# SparkFun_NEO-D9S.net
KiCad netlist of a schematic drawn in EAGLE
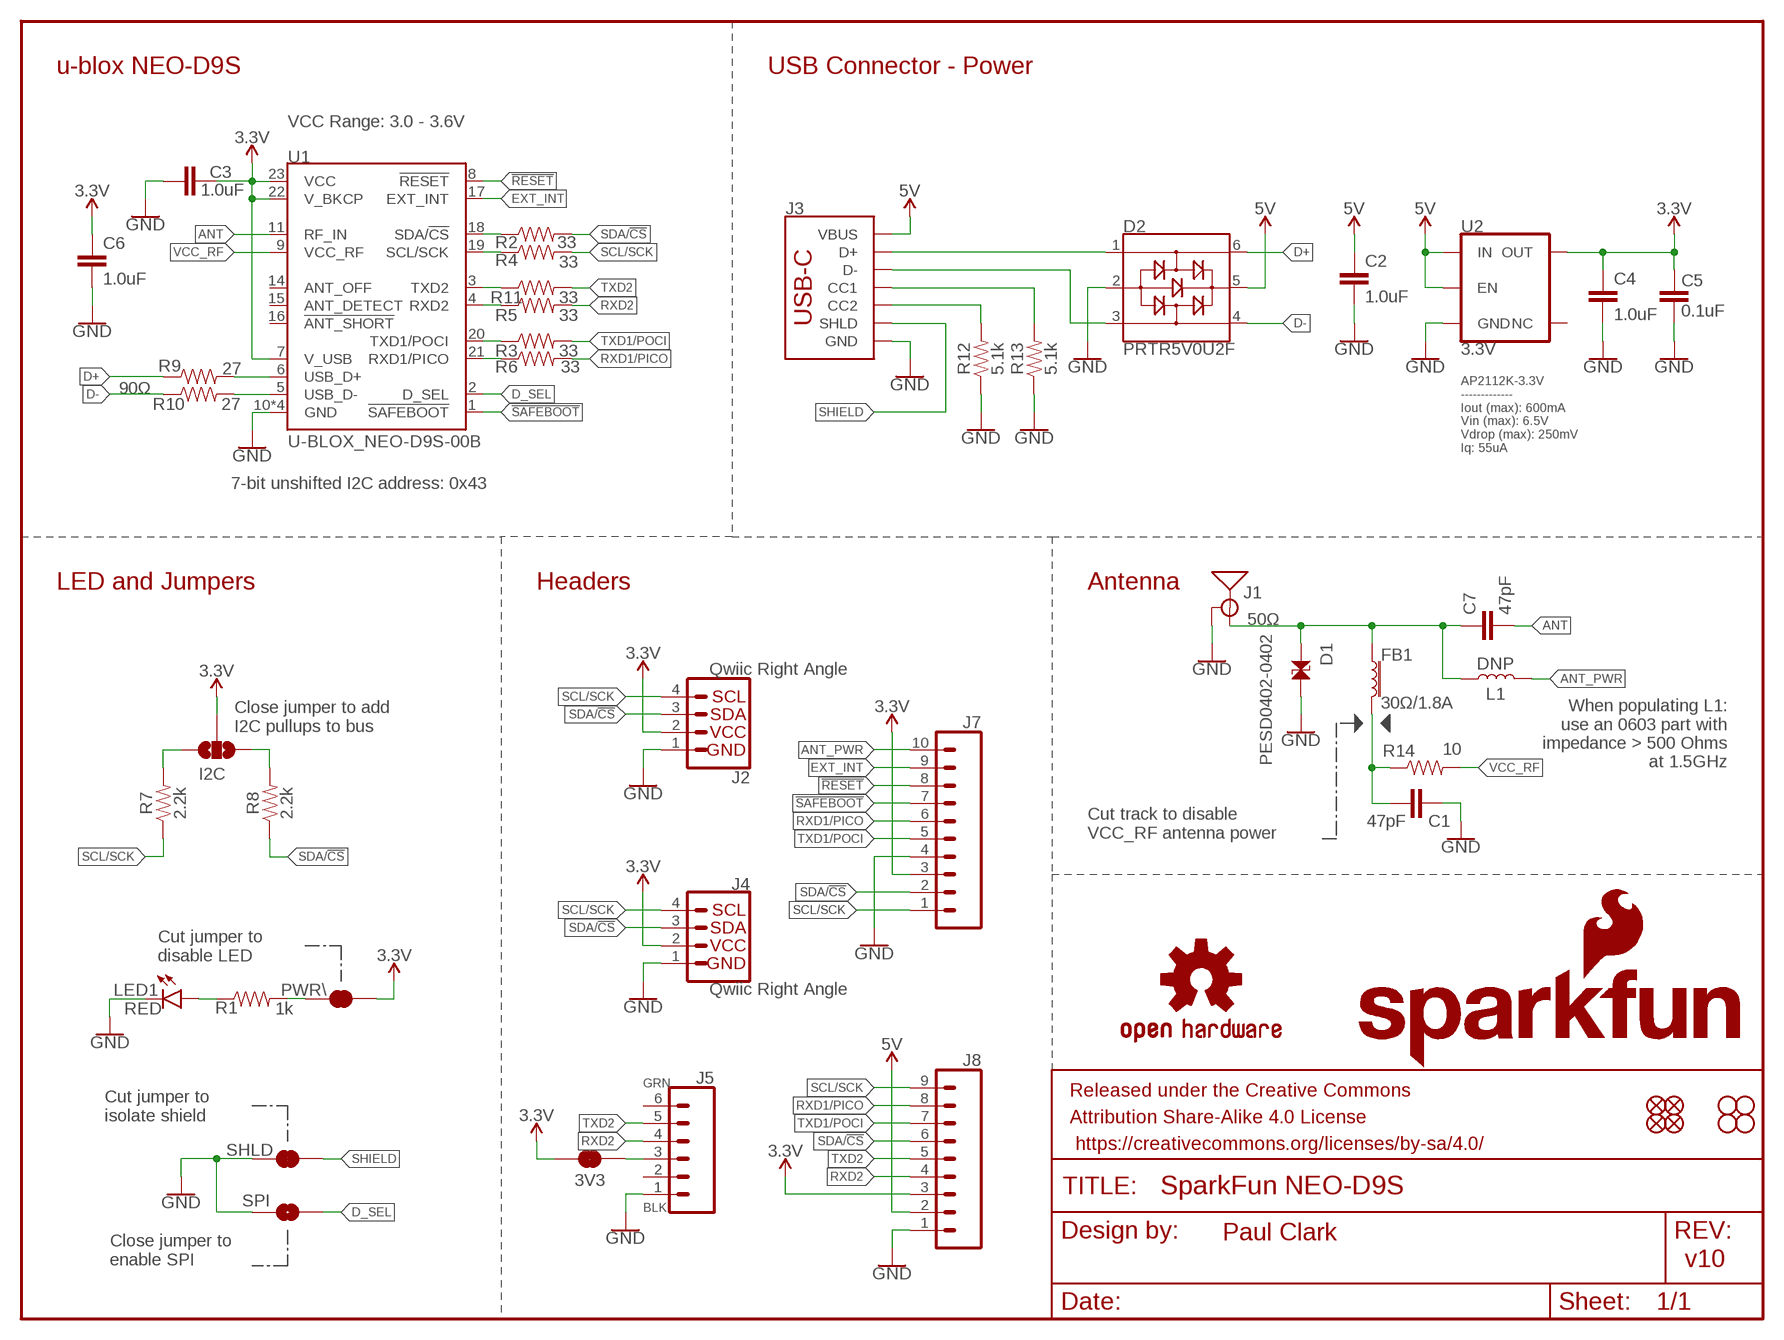
[diagram p0: schematic, sheet 1]

(export (version "E")
  (design (tool "Eeschema 10.0.6"))
  (components
    (comp (ref "3V3")
      (value "JUMPER-SMT_2_NC_TRACE_SILK")
      (footprint "eagle-import:SMT-JUMPER_2_NC_TRACE_SILK")
      (libsource (lib "eagle-import") (part "JUMPER-SMT_2_NC_TRACE_SILK"))
    )
    (comp (ref "C1")
      (value "47pF")
      (footprint "eagle-import:0603")
      (libsource (lib "eagle-import") (part "47PF-0603-50V-5%"))
    )
    (comp (ref "C2")
      (value "1.0uF")
      (footprint "eagle-import:0603")
      (libsource (lib "eagle-import") (part "1.0UF-0603-16V-10%"))
    )
    (comp (ref "C3")
      (value "1.0uF")
      (footprint "eagle-import:0603")
      (libsource (lib "eagle-import") (part "1.0UF-0603-16V-10%"))
    )
    (comp (ref "C4")
      (value "1.0uF")
      (footprint "eagle-import:0603")
      (libsource (lib "eagle-import") (part "1.0UF-0603-16V-10%"))
    )
    (comp (ref "C5")
      (value "0.1uF")
      (footprint "eagle-import:0603")
      (libsource (lib "eagle-import") (part "0.1UF-0603-25V-(+80/-20%)"))
    )
    (comp (ref "C6")
      (value "1.0uF")
      (footprint "eagle-import:0603")
      (libsource (lib "eagle-import") (part "1.0UF-0603-16V-10%"))
    )
    (comp (ref "C7")
      (value "47pF")
      (footprint "eagle-import:0603")
      (libsource (lib "eagle-import") (part "47PF-0603-50V-5%"))
    )
    (comp (ref "D1")
      (value "PESD0402-0402")
      (footprint "eagle-import:0402")
      (fields
        (field (name "DIGIKEY_PART") "PESD0402-140CT-ND")
        (field (name "MOUSE_PART") "650-PESD0402-140")
      )
      (libsource (lib "eagle-import") (part "PESD0402-0402"))
    )
    (comp (ref "D2")
      (value "PRTR5V0U2F")
      (footprint "eagle-import:SOT886")
      (libsource (lib "eagle-import") (part "PRTR5V0U2F"))
    )
    (comp (ref "FB1")
      (value "30Ω/1.8A")
      (footprint "eagle-import:0603")
      (libsource (lib "eagle-import") (part "FERRITE_BEAD-0603"))
    )
    (comp (ref "FRAME1")
      (value "FRAME-LETTER")
      (footprint "eagle-import:CREATIVE_COMMONS")
      (libsource (lib "eagle-import") (part "FRAME-LETTER"))
    )
    (comp (ref "I2C")
      (value "JUMPER-SMT_3_NO_SILK")
      (footprint "eagle-import:SMT-JUMPER_3_NO_SILK")
      (libsource (lib "eagle-import") (part "JUMPER-SMT_3_NO_SILK"))
    )
    (comp (ref "J1")
      (value "ANTENNA-SMA-GROUNDEDEDGE_SMA")
      (footprint "eagle-import:SMA-EDGE")
      (libsource (lib "eagle-import") (part "ANTENNA-SMA-GROUNDEDEDGE_SMA"))
    )
    (comp (ref "J2")
      (value "Qwiic Right Angle")
      (footprint "eagle-import:JST04_1MM_RA")
      (libsource (lib "eagle-import") (part "I2C_STANDARDQWIIC"))
    )
    (comp (ref "J3")
      (value "USB_C_2-LAYER_PADS")
      (footprint "eagle-import:USB-C-16P-2LAYER-PADS")
      (libsource (lib "eagle-import") (part "USB_C_2-LAYER_PADS"))
    )
    (comp (ref "J4")
      (value "Qwiic Right Angle")
      (footprint "eagle-import:JST04_1MM_RA")
      (libsource (lib "eagle-import") (part "I2C_STANDARDQWIIC"))
    )
    (comp (ref "J5")
      (value "CONN_06NO_SILK_FEMALE_PTH")
      (footprint "eagle-import:1X06_NO_SILK")
      (libsource (lib "eagle-import") (part "CONN_06NO_SILK_FEMALE_PTH"))
    )
    (comp (ref "J7")
      (value "CONN_10NO_SILK_PTH_FEMALE")
      (footprint "eagle-import:1X10_NO_SILK")
      (libsource (lib "eagle-import") (part "CONN_10NO_SILK_PTH_FEMALE"))
    )
    (comp (ref "J8")
      (value "CONN_09NO_SILK")
      (footprint "eagle-import:1X09_NO_SILK")
      (libsource (lib "eagle-import") (part "CONN_09NO_SILK"))
    )
    (comp (ref "JP21")
      (value "FIDUCIALUFIDUCIAL")
      (footprint "eagle-import:MICRO-FIDUCIAL")
      (libsource (lib "eagle-import") (part "FIDUCIALUFIDUCIAL"))
    )
    (comp (ref "JP31")
      (value "STAND-OFF")
      (footprint "eagle-import:STAND-OFF")
      (libsource (lib "eagle-import") (part "STAND-OFF"))
    )
    (comp (ref "JP41")
      (value "STAND-OFF")
      (footprint "eagle-import:STAND-OFF")
      (libsource (lib "eagle-import") (part "STAND-OFF"))
    )
    (comp (ref "JP61")
      (value "FIDUCIALUFIDUCIAL")
      (footprint "eagle-import:MICRO-FIDUCIAL")
      (libsource (lib "eagle-import") (part "FIDUCIALUFIDUCIAL"))
    )
    (comp (ref "JP71")
      (value "FIDUCIALUFIDUCIAL")
      (footprint "eagle-import:MICRO-FIDUCIAL")
      (libsource (lib "eagle-import") (part "FIDUCIALUFIDUCIAL"))
    )
    (comp (ref "JP81")
      (value "FIDUCIALUFIDUCIAL")
      (footprint "eagle-import:MICRO-FIDUCIAL")
      (libsource (lib "eagle-import") (part "FIDUCIALUFIDUCIAL"))
    )
    (comp (ref "JP91")
      (value "STAND-OFF")
      (footprint "eagle-import:STAND-OFF")
      (libsource (lib "eagle-import") (part "STAND-OFF"))
    )
    (comp (ref "JP101")
      (value "STAND-OFF")
      (footprint "eagle-import:STAND-OFF")
      (libsource (lib "eagle-import") (part "STAND-OFF"))
    )
    (comp (ref "L1")
      (value "DNP")
      (footprint "eagle-import:0603_NO-CREAM")
      (libsource (lib "eagle-import") (part "DNP-0603_NO-CREAM"))
    )
    (comp (ref "LED1")
      (value "RED")
      (footprint "eagle-import:LED-0603")
      (libsource (lib "eagle-import") (part "LED-RED0603"))
    )
    (comp (ref "LOGO1")
      (value "OSHW-LOGOS")
      (footprint "eagle-import:OSHW-LOGO-S")
      (libsource (lib "eagle-import") (part "OSHW-LOGOS"))
    )
    (comp (ref "LOGO2")
      (value "SFE_LOGO_NAME_FLAME.1_INCH")
      (footprint "eagle-import:SFE_LOGO_NAME_FLAME_.1")
      (libsource (lib "eagle-import") (part "SFE_LOGO_NAME_FLAME.1_INCH"))
    )
    (comp (ref "LOGO3")
      (value "SFE_LOGO_NAME_FLAME.1_INCH")
      (footprint "eagle-import:SFE_LOGO_NAME_FLAME_.1")
      (libsource (lib "eagle-import") (part "SFE_LOGO_NAME_FLAME.1_INCH"))
    )
    (comp (ref "LOGO4")
      (value "OSHW-LOGOS")
      (footprint "eagle-import:OSHW-LOGO-S")
      (libsource (lib "eagle-import") (part "OSHW-LOGOS"))
    )
    (comp (ref "PWR\\")
      (value "JUMPER-SMT_2_NC_TRACE_SILK")
      (footprint "eagle-import:SMT-JUMPER_2_NC_TRACE_SILK")
      (libsource (lib "eagle-import") (part "JUMPER-SMT_2_NC_TRACE_SILK"))
    )
    (comp (ref "R1")
      (value "1k")
      (footprint "eagle-import:0603")
      (libsource (lib "eagle-import") (part "1KOHM-0603-1/10W-1%"))
    )
    (comp (ref "R2")
      (value "33")
      (footprint "eagle-import:0603")
      (libsource (lib "eagle-import") (part "33OHM-0603-1/10W-1%"))
    )
    (comp (ref "R3")
      (value "33")
      (footprint "eagle-import:0603")
      (libsource (lib "eagle-import") (part "33OHM-0603-1/10W-1%"))
    )
    (comp (ref "R4")
      (value "33")
      (footprint "eagle-import:0603")
      (libsource (lib "eagle-import") (part "33OHM-0603-1/10W-1%"))
    )
    (comp (ref "R5")
      (value "33")
      (footprint "eagle-import:0603")
      (libsource (lib "eagle-import") (part "33OHM-0603-1/10W-1%"))
    )
    (comp (ref "R6")
      (value "33")
      (footprint "eagle-import:0603")
      (libsource (lib "eagle-import") (part "33OHM-0603-1/10W-1%"))
    )
    (comp (ref "R7")
      (value "2.2k")
      (footprint "eagle-import:0603")
      (libsource (lib "eagle-import") (part "2.2KOHM-0603-1/10W-1%"))
    )
    (comp (ref "R8")
      (value "2.2k")
      (footprint "eagle-import:0603")
      (libsource (lib "eagle-import") (part "2.2KOHM-0603-1/10W-1%"))
    )
    (comp (ref "R9")
      (value "27")
      (footprint "eagle-import:0603")
      (libsource (lib "eagle-import") (part "27OHM-0603-1/10W-1%"))
    )
    (comp (ref "R10")
      (value "27")
      (footprint "eagle-import:0603")
      (libsource (lib "eagle-import") (part "27OHM-0603-1/10W-1%"))
    )
    (comp (ref "R11")
      (value "33")
      (footprint "eagle-import:0603")
      (libsource (lib "eagle-import") (part "33OHM-0603-1/10W-1%"))
    )
    (comp (ref "R12")
      (value "5.1k")
      (footprint "eagle-import:0603")
      (libsource (lib "eagle-import") (part "5.1KOHM5.1KOHM-0603-1/10W-1%"))
    )
    (comp (ref "R13")
      (value "5.1k")
      (footprint "eagle-import:0603")
      (libsource (lib "eagle-import") (part "5.1KOHM5.1KOHM-0603-1/10W-1%"))
    )
    (comp (ref "R14")
      (value "10")
      (footprint "eagle-import:0603")
      (libsource (lib "eagle-import") (part "10OHM-0603-1/10W-1%"))
    )
    (comp (ref "SHLD")
      (value "JUMPER-SMT_2_NC_TRACE_SILK")
      (footprint "eagle-import:SMT-JUMPER_2_NC_TRACE_SILK")
      (libsource (lib "eagle-import") (part "JUMPER-SMT_2_NC_TRACE_SILK"))
    )
    (comp (ref "SPI")
      (value "JUMPER-SMT_2_NO_SILK")
      (footprint "eagle-import:SMT-JUMPER_2_NO_SILK")
      (libsource (lib "eagle-import") (part "JUMPER-SMT_2_NO_SILK"))
    )
    (comp (ref "U1")
      (value "U-BLOX_NEO-D9S-00B")
      (footprint "eagle-import:NEO-M9N_M8T_M8U_D9S")
      (libsource (lib "eagle-import") (part "U-BLOX_NEO-D9S-00B"))
    )
    (comp (ref "U2")
      (value "3.3V")
      (footprint "eagle-import:SOT23-5")
      (libsource (lib "eagle-import") (part "V_REG_AP2112K-3.3V"))
    )
  )
  (nets
    (net (code "1") (name "/SDA{slash}~{CS}") (class "Default")
      (node (ref "J2") (pin "3") (pinfunction "3_3") (pintype "passive"))
      (node (ref "J4") (pin "3") (pinfunction "3_3") (pintype "passive"))
      (node (ref "J7") (pin "2") (pinfunction "2_2") (pintype "passive"))
      (node (ref "J8") (pin "6") (pinfunction "6_6") (pintype "passive"))
      (node (ref "R2") (pin "2") (pinfunction "2_2") (pintype "passive"))
      (node (ref "R8") (pin "1") (pinfunction "1_1") (pintype "passive"))
    )
    (net (code "2") (name "/~{RESET}") (class "Default")
      (node (ref "J7") (pin "8") (pinfunction "8_8") (pintype "passive"))
      (node (ref "U1") (pin "8") (pinfunction "~{RESET}_8") (pintype "input"))
    )
    (net (code "3") (name "/~{SAFEBOOT}") (class "Default")
      (node (ref "J7") (pin "7") (pinfunction "7_7") (pintype "passive"))
      (node (ref "U1") (pin "1") (pinfunction "~{SAFEBOOT}_1") (pintype "input"))
    )
    (net (code "4") (name "3.3V") (class "Default")
      (node (ref "3V3") (pin "2") (pinfunction "2_2") (pintype "passive"))
      (node (ref "C3") (pin "1") (pinfunction "1_1") (pintype "passive"))
      (node (ref "C4") (pin "1") (pinfunction "1_1") (pintype "passive"))
      (node (ref "C5") (pin "2") (pinfunction "2_2") (pintype "passive"))
      (node (ref "C6") (pin "1") (pinfunction "1_1") (pintype "passive"))
      (node (ref "I2C") (pin "2") (pinfunction "2_2") (pintype "passive"))
      (node (ref "J2") (pin "2") (pinfunction "2_2") (pintype "power_in"))
      (node (ref "J4") (pin "2") (pinfunction "2_2") (pintype "power_in"))
      (node (ref "J7") (pin "3") (pinfunction "3_3") (pintype "passive"))
      (node (ref "J8") (pin "3") (pinfunction "3_3") (pintype "passive"))
      (node (ref "PWR\\") (pin "2") (pinfunction "2_2") (pintype "passive"))
      (node (ref "U1") (pin "22") (pinfunction "V_BKCP_22") (pintype "power_in"))
      (node (ref "U1") (pin "23") (pinfunction "VCC_23") (pintype "power_in"))
      (node (ref "U1") (pin "7") (pinfunction "V_USB_7") (pintype "power_in"))
      (node (ref "U2") (pin "5") (pinfunction "OUT_5") (pintype "passive"))
    )
    (net (code "5") (name "5V") (class "Default")
      (node (ref "C2") (pin "1") (pinfunction "1_1") (pintype "passive"))
      (node (ref "D2") (pin "5") (pinfunction "5_5") (pintype "power_in"))
      (node (ref "J3") (pin "VBUS1") (pinfunction "VBUS_VBUS1") (pintype "bidirectional"))
      (node (ref "J3") (pin "VBUS2") (pinfunction "VBUS_VBUS2") (pintype "bidirectional"))
      (node (ref "J8") (pin "2") (pinfunction "2_2") (pintype "passive"))
      (node (ref "U2") (pin "1") (pinfunction "IN_1") (pintype "input"))
      (node (ref "U2") (pin "3") (pinfunction "EN_3") (pintype "input"))
    )
    (net (code "6") (name "ANT") (class "Default")
      (node (ref "C7") (pin "2") (pinfunction "2_2") (pintype "passive"))
      (node (ref "U1") (pin "11") (pinfunction "RF_IN_11") (pintype "input"))
    )
    (net (code "7") (name "ANT_PWR") (class "Default")
      (node (ref "J7") (pin "10") (pinfunction "10_10") (pintype "passive"))
      (node (ref "L1") (pin "2") (pinfunction "2_2") (pintype "passive"))
    )
    (net (code "8") (name "D+") (class "Default")
      (node (ref "D2") (pin "6") (pinfunction "6_6") (pintype "bidirectional"))
      (node (ref "R9") (pin "1") (pinfunction "1_1") (pintype "passive"))
    )
    (net (code "9") (name "D-") (class "Default")
      (node (ref "D2") (pin "4") (pinfunction "4_4") (pintype "bidirectional"))
      (node (ref "R10") (pin "1") (pinfunction "1_1") (pintype "passive"))
    )
    (net (code "10") (name "D_SEL") (class "Default")
      (node (ref "SPI") (pin "2") (pinfunction "2_2") (pintype "passive"))
      (node (ref "U1") (pin "2") (pinfunction "D_SEL_2") (pintype "input"))
    )
    (net (code "11") (name "EXT_INT") (class "Default")
      (node (ref "J7") (pin "9") (pinfunction "9_9") (pintype "passive"))
      (node (ref "U1") (pin "17") (pinfunction "EXT_INT_17") (pintype "input"))
    )
    (net (code "12") (name "GND") (class "Default")
      (node (ref "C1") (pin "2") (pinfunction "2_2") (pintype "passive"))
      (node (ref "C2") (pin "2") (pinfunction "2_2") (pintype "passive"))
      (node (ref "C3") (pin "2") (pinfunction "2_2") (pintype "passive"))
      (node (ref "C4") (pin "2") (pinfunction "2_2") (pintype "passive"))
      (node (ref "C5") (pin "1") (pinfunction "1_1") (pintype "passive"))
      (node (ref "C6") (pin "2") (pinfunction "2_2") (pintype "passive"))
      (node (ref "D1") (pin "2") (pinfunction "2_2") (pintype "bidirectional"))
      (node (ref "D2") (pin "2") (pinfunction "2_2") (pintype "power_in"))
      (node (ref "J1") (pin "GND@0") (pinfunction "GND_GND@0") (pintype "bidirectional"))
      (node (ref "J1") (pin "GND@1") (pinfunction "GND_GND@1") (pintype "bidirectional"))
      (node (ref "J1") (pin "GND@2") (pinfunction "GND_GND@2") (pintype "bidirectional"))
      (node (ref "J1") (pin "GND@3") (pinfunction "GND_GND@3") (pintype "bidirectional"))
      (node (ref "J2") (pin "1") (pinfunction "1_1") (pintype "power_in"))
      (node (ref "J3") (pin "GND") (pinfunction "GND_GND") (pintype "bidirectional"))
      (node (ref "J3") (pin "GND2") (pinfunction "GND_GND2") (pintype "bidirectional"))
      (node (ref "J4") (pin "1") (pinfunction "1_1") (pintype "power_in"))
      (node (ref "J5") (pin "1") (pinfunction "1_1") (pintype "passive"))
      (node (ref "J7") (pin "4") (pinfunction "4_4") (pintype "passive"))
      (node (ref "J8") (pin "1") (pinfunction "1_1") (pintype "passive"))
      (node (ref "LED1") (pin "C") (pinfunction "C_C") (pintype "passive"))
      (node (ref "R12") (pin "1") (pinfunction "1_1") (pintype "passive"))
      (node (ref "R13") (pin "1") (pinfunction "1_1") (pintype "passive"))
      (node (ref "SHLD") (pin "1") (pinfunction "1_1") (pintype "passive"))
      (node (ref "SPI") (pin "1") (pinfunction "1_1") (pintype "passive"))
      (node (ref "U1") (pin "10") (pinfunction "GND_10") (pintype "power_in"))
      (node (ref "U1") (pin "12") (pinfunction "GND_12") (pintype "power_in"))
      (node (ref "U1") (pin "13") (pinfunction "GND_13") (pintype "power_in"))
      (node (ref "U1") (pin "24") (pinfunction "GND_24") (pintype "power_in"))
      (node (ref "U2") (pin "2") (pinfunction "GND_2") (pintype "input"))
    )
    (net (code "13") (name "Net-(3V3-Pad1)") (class "Default")
      (node (ref "3V3") (pin "1") (pinfunction "1_1") (pintype "passive"))
      (node (ref "J5") (pin "3") (pinfunction "3_3") (pintype "passive"))
    )
    (net (code "14") (name "Net-(C1-Pad1)") (class "Default")
      (node (ref "C1") (pin "1") (pinfunction "1_1") (pintype "passive"))
      (node (ref "FB1") (pin "2") (pinfunction "2_2") (pintype "passive"))
      (node (ref "R14") (pin "1") (pinfunction "1_1") (pintype "passive"))
    )
    (net (code "15") (name "Net-(D2-Pad1)") (class "Default")
      (node (ref "D2") (pin "1") (pinfunction "1_1") (pintype "bidirectional"))
      (node (ref "J3") (pin "A6") (pinfunction "D+_A6") (pintype "bidirectional"))
      (node (ref "J3") (pin "B6") (pinfunction "D+_B6") (pintype "bidirectional"))
    )
    (net (code "16") (name "Net-(D2-Pad3)") (class "Default")
      (node (ref "D2") (pin "3") (pinfunction "3_3") (pintype "bidirectional"))
      (node (ref "J3") (pin "A7") (pinfunction "D-_A7") (pintype "bidirectional"))
      (node (ref "J3") (pin "B7") (pinfunction "D-_B7") (pintype "bidirectional"))
    )
    (net (code "17") (name "Net-(I2C-Pad1)") (class "Default")
      (node (ref "I2C") (pin "1") (pinfunction "1_1") (pintype "passive"))
      (node (ref "R8") (pin "2") (pinfunction "2_2") (pintype "passive"))
    )
    (net (code "18") (name "Net-(I2C-Pad3)") (class "Default")
      (node (ref "I2C") (pin "3") (pinfunction "3_3") (pintype "passive"))
      (node (ref "R7") (pin "2") (pinfunction "2_2") (pintype "passive"))
    )
    (net (code "19") (name "Net-(J1-SIGNAL)") (class "Default")
      (node (ref "C7") (pin "1") (pinfunction "1_1") (pintype "passive"))
      (node (ref "D1") (pin "1") (pinfunction "1_1") (pintype "bidirectional"))
      (node (ref "FB1") (pin "1") (pinfunction "1_1") (pintype "passive"))
      (node (ref "J1") (pin "SIG") (pinfunction "SIGNAL_SIG") (pintype "bidirectional"))
      (node (ref "L1") (pin "1") (pinfunction "1_1") (pintype "passive"))
    )
    (net (code "20") (name "Net-(J3-CC1)") (class "Default")
      (node (ref "J3") (pin "A5") (pinfunction "CC1_A5") (pintype "bidirectional"))
      (node (ref "R13") (pin "2") (pinfunction "2_2") (pintype "passive"))
    )
    (net (code "21") (name "Net-(J3-CC2)") (class "Default")
      (node (ref "J3") (pin "B5") (pinfunction "CC2_B5") (pintype "bidirectional"))
      (node (ref "R12") (pin "2") (pinfunction "2_2") (pintype "passive"))
    )
    (net (code "22") (name "Net-(LED1-PadA)") (class "Default")
      (node (ref "LED1") (pin "A") (pinfunction "A_A") (pintype "passive"))
      (node (ref "R1") (pin "1") (pinfunction "1_1") (pintype "passive"))
    )
    (net (code "23") (name "Net-(PWR\\-Pad1)") (class "Default")
      (node (ref "PWR\\") (pin "1") (pinfunction "1_1") (pintype "passive"))
      (node (ref "R1") (pin "2") (pinfunction "2_2") (pintype "passive"))
    )
    (net (code "24") (name "Net-(U1-RXD1{slash}PICO)") (class "Default")
      (node (ref "R6") (pin "1") (pinfunction "1_1") (pintype "passive"))
      (node (ref "U1") (pin "21") (pinfunction "RXD1/PICO_21") (pintype "input"))
    )
    (net (code "25") (name "Net-(U1-RXD2)") (class "Default")
      (node (ref "R5") (pin "1") (pinfunction "1_1") (pintype "passive"))
      (node (ref "U1") (pin "4") (pinfunction "RXD2_4") (pintype "input"))
    )
    (net (code "26") (name "Net-(U1-SCL{slash}SCK)") (class "Default")
      (node (ref "R4") (pin "1") (pinfunction "1_1") (pintype "passive"))
      (node (ref "U1") (pin "19") (pinfunction "SCL/SCK_19") (pintype "bidirectional"))
    )
    (net (code "27") (name "Net-(U1-SDA{slash}~{CS})") (class "Default")
      (node (ref "R2") (pin "1") (pinfunction "1_1") (pintype "passive"))
      (node (ref "U1") (pin "18") (pinfunction "SDA/~{CS}_18") (pintype "bidirectional"))
    )
    (net (code "28") (name "Net-(U1-TXD1{slash}POCI)") (class "Default")
      (node (ref "R3") (pin "1") (pinfunction "1_1") (pintype "passive"))
      (node (ref "U1") (pin "20") (pinfunction "TXD1/POCI_20") (pintype "output"))
    )
    (net (code "29") (name "Net-(U1-TXD2)") (class "Default")
      (node (ref "R11") (pin "1") (pinfunction "1_1") (pintype "passive"))
      (node (ref "U1") (pin "3") (pinfunction "TXD2_3") (pintype "output"))
    )
    (net (code "30") (name "Net-(U1-USB_D+)") (class "Default")
      (node (ref "R9") (pin "2") (pinfunction "2_2") (pintype "passive"))
      (node (ref "U1") (pin "6") (pinfunction "USB_D+_6") (pintype "bidirectional"))
    )
    (net (code "31") (name "Net-(U1-USB_D-)") (class "Default")
      (node (ref "R10") (pin "2") (pinfunction "2_2") (pintype "passive"))
      (node (ref "U1") (pin "5") (pinfunction "USB_D-_5") (pintype "bidirectional"))
    )
    (net (code "32") (name "RXD1{slash}PICO") (class "Default")
      (node (ref "J7") (pin "6") (pinfunction "6_6") (pintype "passive"))
      (node (ref "J8") (pin "8") (pinfunction "8_8") (pintype "passive"))
      (node (ref "R6") (pin "2") (pinfunction "2_2") (pintype "passive"))
    )
    (net (code "33") (name "RXD2") (class "Default")
      (node (ref "J5") (pin "4") (pinfunction "4_4") (pintype "passive"))
      (node (ref "J8") (pin "4") (pinfunction "4_4") (pintype "passive"))
      (node (ref "R5") (pin "2") (pinfunction "2_2") (pintype "passive"))
    )
    (net (code "34") (name "SCL{slash}SCK") (class "Default")
      (node (ref "J2") (pin "4") (pinfunction "4_4") (pintype "passive"))
      (node (ref "J4") (pin "4") (pinfunction "4_4") (pintype "passive"))
      (node (ref "J7") (pin "1") (pinfunction "1_1") (pintype "passive"))
      (node (ref "J8") (pin "9") (pinfunction "9_9") (pintype "passive"))
      (node (ref "R4") (pin "2") (pinfunction "2_2") (pintype "passive"))
      (node (ref "R7") (pin "1") (pinfunction "1_1") (pintype "passive"))
    )
    (net (code "35") (name "SHIELD") (class "Default")
      (node (ref "J3") (pin "SHLD1") (pinfunction "SHLD_SHLD1") (pintype "bidirectional"))
      (node (ref "J3") (pin "SHLD2") (pinfunction "SHLD_SHLD2") (pintype "bidirectional"))
      (node (ref "J3") (pin "SHLD3") (pinfunction "SHLD_SHLD3") (pintype "bidirectional"))
      (node (ref "J3") (pin "SHLD4") (pinfunction "SHLD_SHLD4") (pintype "bidirectional"))
      (node (ref "SHLD") (pin "2") (pinfunction "2_2") (pintype "passive"))
    )
    (net (code "36") (name "TXD1{slash}POCI") (class "Default")
      (node (ref "J7") (pin "5") (pinfunction "5_5") (pintype "passive"))
      (node (ref "J8") (pin "7") (pinfunction "7_7") (pintype "passive"))
      (node (ref "R3") (pin "2") (pinfunction "2_2") (pintype "passive"))
    )
    (net (code "37") (name "TXD2") (class "Default")
      (node (ref "J5") (pin "5") (pinfunction "5_5") (pintype "passive"))
      (node (ref "J8") (pin "5") (pinfunction "5_5") (pintype "passive"))
      (node (ref "R11") (pin "2") (pinfunction "2_2") (pintype "passive"))
    )
    (net (code "38") (name "VCC_RF") (class "Default")
      (node (ref "R14") (pin "2") (pinfunction "2_2") (pintype "passive"))
      (node (ref "U1") (pin "9") (pinfunction "VCC_RF_9") (pintype "output"))
    )
    (net (code "39") (name "unconnected-(J5-Pad2)") (class "Default")
      (node (ref "J5") (pin "2") (pinfunction "2_2") (pintype "passive"))
    )
    (net (code "40") (name "unconnected-(J5-Pad6)") (class "Default")
      (node (ref "J5") (pin "6") (pinfunction "6_6") (pintype "passive"))
    )
    (net (code "41") (name "unconnected-(U1-ANT_DETECT-Pad15)") (class "Default")
      (node (ref "U1") (pin "15") (pinfunction "ANT_DETECT_15") (pintype "input"))
    )
    (net (code "42") (name "unconnected-(U1-ANT_OFF-Pad14)") (class "Default")
      (node (ref "U1") (pin "14") (pinfunction "ANT_OFF_14") (pintype "output"))
    )
    (net (code "43") (name "unconnected-(U1-~{ANT_SHORT}-Pad16)") (class "Default")
      (node (ref "U1") (pin "16") (pinfunction "~{ANT_SHORT}_16") (pintype "output"))
    )
    (net (code "44") (name "unconnected-(U2-NC-Pad4)") (class "Default")
      (node (ref "U2") (pin "4") (pinfunction "NC_4") (pintype "no_connect"))
    )
  )
)
